# LFO_Schematic_Sheet_2.net
KiCad netlist of a schematic drawn in Altium Designer
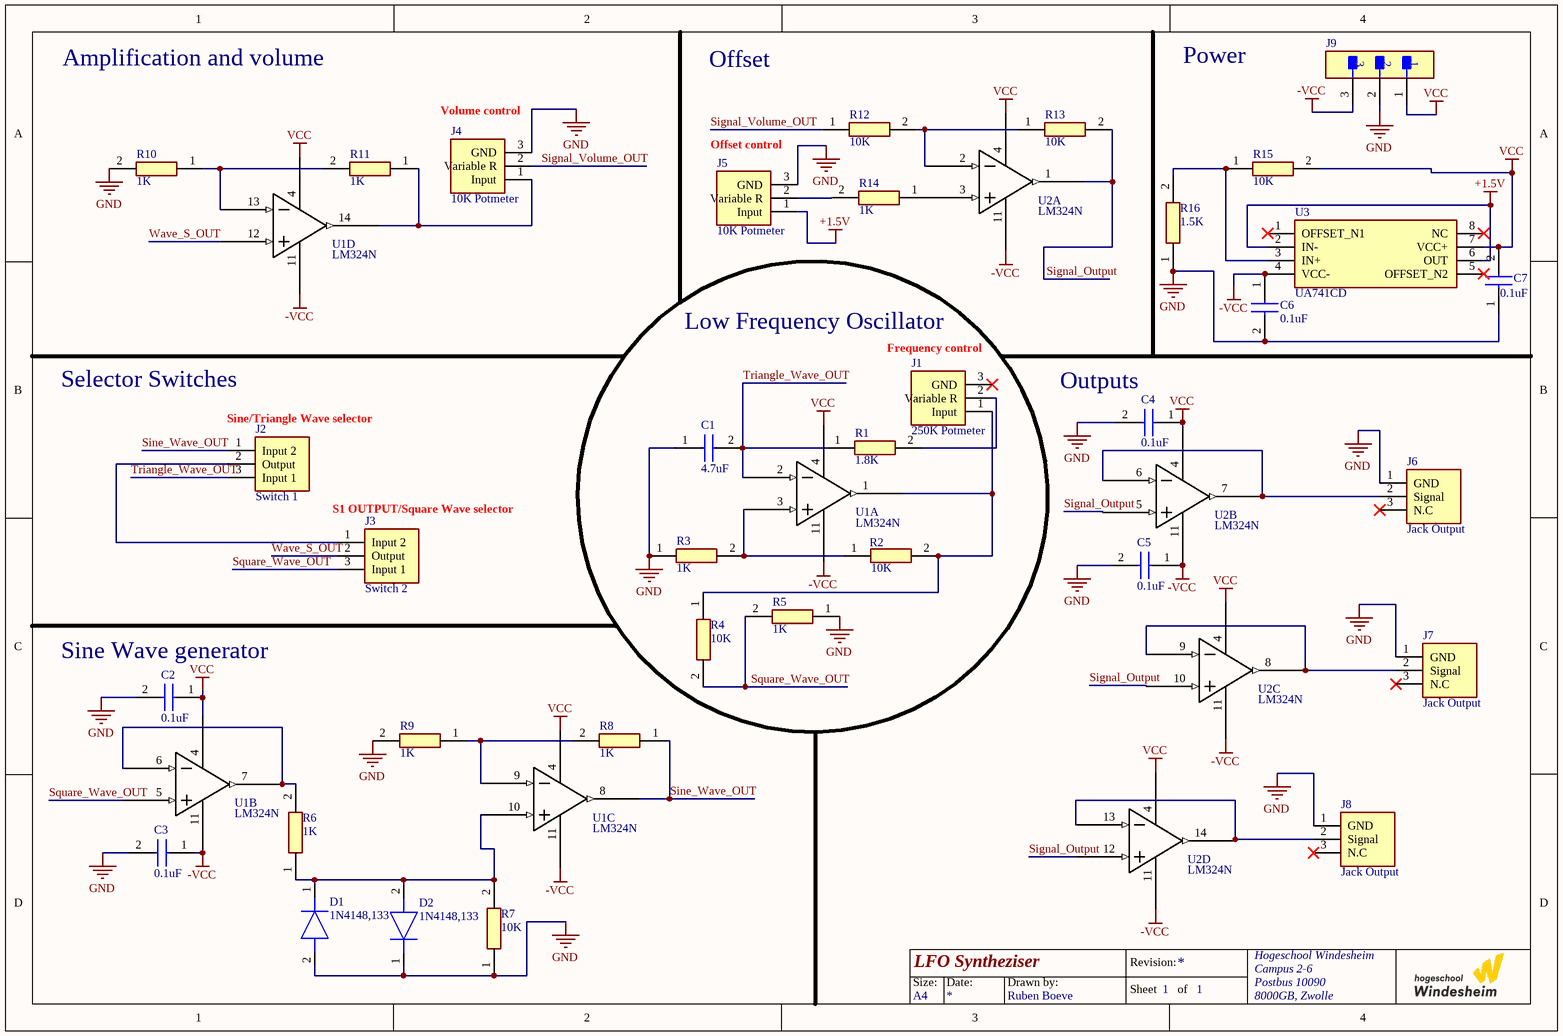
[diagram p0: LFO Schematic Sheet.2.SchDoc]

(export (version "E")
  (design (tool "Eeschema 10.0.6"))
  (components
    (comp (ref "C1")
      (value "4.7uF")
      (footprint "SamacSys:CAPC3216X180N")
      (description "Capacitor")
      (fields
        (field (name "MANUFACTURER_PART_NUMBER") "KGM31AR71H475KU")
        (field (name "MOUSER PART NUMBER") "581-KGM31AR71H475KU")
      )
      (libsource (lib "*") (part "KGM31AR71H475KU"))
    )
    (comp (ref "C2")
      (value "0.1uF")
      (footprint "SamacSys:C1206")
      (description "Capacitor")
      (fields
        (field (name "MANUFACTURER_PART_NUMBER") "C1206F104M4RACTU")
        (field (name "MOUSER PART NUMBER") "80-C1206F104M4R")
      )
      (libsource (lib "*") (part "C1206F104M4RACTU"))
    )
    (comp (ref "C3")
      (value "0.1uF")
      (footprint "SamacSys:C1206")
      (description "Capacitor")
      (fields
        (field (name "MANUFACTURER_PART_NUMBER") "C1206F104M4RACTU")
        (field (name "MOUSER PART NUMBER") "80-C1206F104M4R")
      )
      (libsource (lib "*") (part "C1206F104M4RACTU"))
    )
    (comp (ref "C4")
      (value "0.1uF")
      (footprint "SamacSys:C1206")
      (description "Capacitor")
      (fields
        (field (name "MANUFACTURER_PART_NUMBER") "C1206F104M4RACTU")
        (field (name "MOUSER PART NUMBER") "80-C1206F104M4R")
      )
      (libsource (lib "*") (part "C1206F104M4RACTU"))
    )
    (comp (ref "C5")
      (value "0.1uF")
      (footprint "SamacSys:C1206")
      (description "Capacitor")
      (fields
        (field (name "MANUFACTURER_PART_NUMBER") "C1206F104M4RACTU")
        (field (name "MOUSER PART NUMBER") "80-C1206F104M4R")
      )
      (libsource (lib "*") (part "C1206F104M4RACTU"))
    )
    (comp (ref "C6")
      (value "0.1uF")
      (footprint "SamacSys:C1206")
      (description "Capacitor")
      (fields
        (field (name "MANUFACTURER_PART_NUMBER") "C1206F104M4RACTU")
        (field (name "MOUSER PART NUMBER") "80-C1206F104M4R")
      )
      (libsource (lib "*") (part "C1206F104M4RACTU"))
    )
    (comp (ref "C7")
      (value "0.1uF")
      (footprint "SamacSys:C1206")
      (description "Capacitor")
      (fields
        (field (name "MANUFACTURER_PART_NUMBER") "C1206F104M4RACTU")
        (field (name "MOUSER PART NUMBER") "80-C1206F104M4R")
      )
      (libsource (lib "*") (part "C1206F104M4RACTU"))
    )
    (comp (ref "D1")
      (value "1N4148,133")
      (footprint "SamacSys:DIOAD1165W56L425D185")
      (description "Diode")
      (fields (field (name "MOUSER PART NUMBER") "771-1N4148,133"))
      (libsource (lib "*") (part "1N4148,133"))
    )
    (comp (ref "D2")
      (value "1N4148,133")
      (footprint "SamacSys:DIOAD1165W56L425D185")
      (description "Diode")
      (fields (field (name "MOUSER PART NUMBER") "771-1N4148,133"))
      (libsource (lib "*") (part "1N4148,133"))
    )
    (comp (ref "J1")
      (value "250K Potmeter")
      (footprint "SamacSys:SHDR3W50P0X200_1X3_650X240X440P")
      (description "Connector")
      (fields
        (field (name "MANUFACTURER_PART_NUMBER") "M22-7130342")
        (field (name "MOUSER PART NUMBER") "855-M22-7130342")
      )
      (libsource (lib "*") (part "M22-7130342"))
    )
    (comp (ref "J2")
      (value "Switch 1")
      (footprint "SamacSys:SHDR3W50P0X200_1X3_650X240X440P")
      (description "Connector")
      (fields
        (field (name "MANUFACTURER_PART_NUMBER") "M22-7130342")
        (field (name "MOUSER PART NUMBER") "855-M22-7130342")
      )
      (libsource (lib "") (part "M22-7130342_1"))
    )
    (comp (ref "J3")
      (value "Switch 2")
      (footprint "SamacSys:SHDR3W50P0X200_1X3_650X240X440P")
      (description "Connector")
      (fields
        (field (name "MANUFACTURER_PART_NUMBER") "M22-7130342")
        (field (name "MOUSER PART NUMBER") "855-M22-7130342")
      )
      (libsource (lib "") (part "M22-7130342_1"))
    )
    (comp (ref "J4")
      (value "10K Potmeter")
      (footprint "SamacSys:SHDR3W50P0X200_1X3_650X240X440P")
      (description "Connector")
      (fields
        (field (name "MANUFACTURER_PART_NUMBER") "M22-7130342")
        (field (name "MOUSER PART NUMBER") "855-M22-7130342")
      )
      (libsource (lib "*") (part "M22-7130342"))
    )
    (comp (ref "J5")
      (value "10K Potmeter")
      (footprint "SamacSys:SHDR3W50P0X200_1X3_650X240X440P")
      (description "Connector")
      (fields
        (field (name "MANUFACTURER_PART_NUMBER") "M22-7130342")
        (field (name "MOUSER PART NUMBER") "855-M22-7130342")
      )
      (libsource (lib "*") (part "M22-7130342"))
    )
    (comp (ref "J6")
      (value "Jack Output")
      (footprint "SamacSys:SHDR3W50P0X200_1X3_650X240X440P")
      (description "Connector")
      (fields
        (field (name "MANUFACTURER_PART_NUMBER") "M22-7130342")
        (field (name "MOUSER PART NUMBER") "855-M22-7130342")
      )
      (libsource (lib "") (part "M22-7130342_1"))
    )
    (comp (ref "J7")
      (value "Jack Output")
      (footprint "SamacSys:SHDR3W50P0X200_1X3_650X240X440P")
      (description "Connector")
      (fields
        (field (name "MANUFACTURER_PART_NUMBER") "M22-7130342")
        (field (name "MOUSER PART NUMBER") "855-M22-7130342")
      )
      (libsource (lib "") (part "M22-7130342_1"))
    )
    (comp (ref "J8")
      (value "Jack Output")
      (footprint "SamacSys:SHDR3W50P0X200_1X3_650X240X440P")
      (description "Connector")
      (fields
        (field (name "MANUFACTURER_PART_NUMBER") "M22-7130342")
        (field (name "MOUSER PART NUMBER") "855-M22-7130342")
      )
      (libsource (lib "") (part "M22-7130342_1"))
    )
    (comp (ref "J9")
      (value "B3B-XH-A(LF)(SN)")
      (footprint "FP-B3B-XH-A_LF_SN-MFG")
      (description "CONN HEADER VERT 3POS 2.5MM")
      (libsource (lib "Altium Content Vault") (part "0d3f023dd272f625e17a2be33dea85f"))
    )
    (comp (ref "R1")
      (value "1.8K")
      (footprint "SamacSys:ERJS08_U08_(1206)")
      (description "Moet 1.8K zijn")
      (fields (field (name "MANUFACTURER_PART_NUMBER") "ERJ-S08F1101V"))
      (libsource (lib "*") (part "ERJ-S08F1101V"))
    )
    (comp (ref "R2")
      (value "10K")
      (footprint "SamacSys:RESC3116X65N")
      (description "Resistor 1206")
      (fields
        (field (name "MANUFACTURER_PART_NUMBER") "RC1206FR-0710KL")
        (field (name "MOUSER PART NUMBER") "603-RC1206FR-0710KL")
      )
      (libsource (lib "") (part "RC1206FR-0710KL_2"))
    )
    (comp (ref "R3")
      (value "1K")
      (footprint "SamacSys:RCC1206_e3")
      (description "Resistor")
      (fields
        (field (name "MANUFACTURER_PART_NUMBER") "RCC12061K00FKEA")
        (field (name "MOUSER PART NUMBER") "71-RCC12061K00FKEA")
      )
      (libsource (lib "") (part "RCC12061K00FKEA_1"))
    )
    (comp (ref "R4")
      (value "10K")
      (footprint "SamacSys:RESC3116X65N")
      (description "Resistor 1206")
      (fields
        (field (name "MANUFACTURER_PART_NUMBER") "RC1206FR-0710KL")
        (field (name "MOUSER PART NUMBER") "603-RC1206FR-0710KL")
      )
      (libsource (lib "*") (part "RC1206FR-0710KL"))
    )
    (comp (ref "R5")
      (value "1K")
      (footprint "SamacSys:RCC1206_e3")
      (description "Resistor")
      (fields
        (field (name "MANUFACTURER_PART_NUMBER") "RCC12061K00FKEA")
        (field (name "MOUSER PART NUMBER") "71-RCC12061K00FKEA")
      )
      (libsource (lib "*") (part "RCC12061K00FKEA"))
    )
    (comp (ref "R6")
      (value "1K")
      (footprint "SamacSys:RCC1206_e3")
      (description "Resistor")
      (fields
        (field (name "MANUFACTURER_PART_NUMBER") "RCC12061K00FKEA")
        (field (name "MOUSER PART NUMBER") "71-RCC12061K00FKEA")
      )
      (libsource (lib "") (part "RCC12061K00FKEA_2"))
    )
    (comp (ref "R7")
      (value "10K")
      (footprint "SamacSys:RESC3116X65N")
      (description "Resistor 1206")
      (fields
        (field (name "MANUFACTURER_PART_NUMBER") "RC1206FR-0710KL")
        (field (name "MOUSER PART NUMBER") "603-RC1206FR-0710KL")
      )
      (libsource (lib "") (part "RC1206FR-0710KL_1"))
    )
    (comp (ref "R8")
      (value "1K")
      (footprint "SamacSys:RCC1206_e3")
      (description "Resistor")
      (fields
        (field (name "MANUFACTURER_PART_NUMBER") "RCC12061K00FKEA")
        (field (name "MOUSER PART NUMBER") "71-RCC12061K00FKEA")
      )
      (libsource (lib "*") (part "RCC12061K00FKEA"))
    )
    (comp (ref "R9")
      (value "1K")
      (footprint "SamacSys:RCC1206_e3")
      (description "Resistor")
      (fields
        (field (name "MANUFACTURER_PART_NUMBER") "RCC12061K00FKEA")
        (field (name "MOUSER PART NUMBER") "71-RCC12061K00FKEA")
      )
      (libsource (lib "*") (part "RCC12061K00FKEA"))
    )
    (comp (ref "R10")
      (value "1K")
      (footprint "SamacSys:RCC1206_e3")
      (description "Resistor")
      (fields
        (field (name "MANUFACTURER_PART_NUMBER") "RCC12061K00FKEA")
        (field (name "MOUSER PART NUMBER") "71-RCC12061K00FKEA")
      )
      (libsource (lib "*") (part "RCC12061K00FKEA"))
    )
    (comp (ref "R11")
      (value "1K")
      (footprint "SamacSys:RCC1206_e3")
      (description "Resistor")
      (fields
        (field (name "MANUFACTURER_PART_NUMBER") "RCC12061K00FKEA")
        (field (name "MOUSER PART NUMBER") "71-RCC12061K00FKEA")
      )
      (libsource (lib "*") (part "RCC12061K00FKEA"))
    )
    (comp (ref "R12")
      (value "10K")
      (footprint "SamacSys:RESC3116X65N")
      (description "Resistor 1206")
      (fields
        (field (name "MANUFACTURER_PART_NUMBER") "RC1206FR-0710KL")
        (field (name "MOUSER PART NUMBER") "603-RC1206FR-0710KL")
      )
      (libsource (lib "") (part "RC1206FR-0710KL_2"))
    )
    (comp (ref "R13")
      (value "10K")
      (footprint "SamacSys:RESC3116X65N")
      (description "Resistor 1206")
      (fields
        (field (name "MANUFACTURER_PART_NUMBER") "RC1206FR-0710KL")
        (field (name "MOUSER PART NUMBER") "603-RC1206FR-0710KL")
      )
      (libsource (lib "") (part "RC1206FR-0710KL_2"))
    )
    (comp (ref "R14")
      (value "1K")
      (footprint "SamacSys:RCC1206_e3")
      (description "Resistor")
      (fields
        (field (name "MANUFACTURER_PART_NUMBER") "RCC12061K00FKEA")
        (field (name "MOUSER PART NUMBER") "71-RCC12061K00FKEA")
      )
      (libsource (lib "*") (part "RCC12061K00FKEA"))
    )
    (comp (ref "R15")
      (value "10K")
      (footprint "SamacSys:RESC3116X65N")
      (description "Resistor 1206")
      (fields
        (field (name "MANUFACTURER_PART_NUMBER") "RC1206FR-0710KL")
        (field (name "MOUSER PART NUMBER") "603-RC1206FR-0710KL")
      )
      (libsource (lib "") (part "RC1206FR-0710KL_2"))
    )
    (comp (ref "R16")
      (value "1.5K")
      (footprint "SamacSys:RESC3246X60N")
      (description "Resistor")
      (fields (field (name "MANUFACTURER_PART_NUMBER") "CRCW12181K50JNEK"))
      (libsource (lib "*") (part "CRCW12181K50JNEK"))
    )
    (comp (ref "U1")
      (value "LM324N")
      (footprint "SOIC127P600X175-14N")
      (description "Quad Op-Amp")
      (fields
        (field (name "MANUFACTURER_PART_NUMBER") "LM324M/NOPB")
        (field (name "MOUSER PART NUMBER") "926-LM324M/NOPB")
      )
      (libsource (lib "MyLibrary") (part "LM324N"))
    )
    (comp (ref "U2")
      (value "LM324N")
      (footprint "SOIC127P600X175-14N")
      (description "Quad Op-Amp")
      (fields
        (field (name "MANUFACTURER_PART_NUMBER") "LM324M/NOPB")
        (field (name "MOUSER PART NUMBER") "926-LM324M/NOPB")
      )
      (libsource (lib "MyLibrary") (part "LM324N"))
    )
    (comp (ref "U3")
      (value "UA741CD")
      (footprint "SamacSys:SOIC127P600X175-8N")
      (description "Integrated Circuit")
      (fields (field (name "MOUSER PART NUMBER") "595-UA741CD"))
      (libsource (lib "*") (part "UA741CD"))
    )
  )
  (nets
    (net (code "1") (name "+1.5V") (class "Default")
      (node (ref "J5") (pin "1") (pinfunction "Input_1") (pintype "passive"))
      (node (ref "U3") (pin "2") (pinfunction "IN-_2") (pintype "passive"))
      (node (ref "U3") (pin "6") (pinfunction "OUT_6") (pintype "passive"))
    )
    (net (code "2") (name "-VCC") (class "Default")
      (node (ref "C3") (pin "1") (pinfunction "1_1") (pintype "passive"))
      (node (ref "C5") (pin "1") (pinfunction "1_1") (pintype "passive"))
      (node (ref "C6") (pin "1") (pinfunction "1_1") (pintype "passive"))
      (node (ref "J9") (pin "3") (pinfunction "3_3") (pintype "passive"))
      (node (ref "U1") (pin "11") (pinfunction "GND_11") (pintype "power_in"))
      (node (ref "U2") (pin "11") (pinfunction "GND_11") (pintype "power_in"))
      (node (ref "U3") (pin "4") (pinfunction "VCC-_4") (pintype "passive"))
    )
    (net (code "3") (name "/Signal_Output") (class "Default")
      (node (ref "R13") (pin "2") (pinfunction "2_2") (pintype "passive"))
      (node (ref "U2") (pin "1") (pinfunction "Out_1") (pintype "output"))
      (node (ref "U2") (pin "10") (pinfunction "+_10") (pintype "input"))
      (node (ref "U2") (pin "12") (pinfunction "+_12") (pintype "input"))
      (node (ref "U2") (pin "5") (pinfunction "+_5") (pintype "input"))
    )
    (net (code "4") (name "/Signal_Volume_OUT") (class "Default")
      (node (ref "J4") (pin "2") (pinfunction "Variable_R_2") (pintype "passive"))
      (node (ref "R12") (pin "1") (pinfunction "1_1") (pintype "passive"))
    )
    (net (code "5") (name "/Sine_Wave_OUT") (class "Default")
      (node (ref "J2") (pin "1") (pinfunction "Input_2_1") (pintype "passive"))
      (node (ref "R8") (pin "1") (pinfunction "1_1") (pintype "passive"))
      (node (ref "U1") (pin "8") (pinfunction "Out_8") (pintype "output"))
    )
    (net (code "6") (name "/Square_Wave_OUT") (class "Default")
      (node (ref "J3") (pin "3") (pinfunction "Input_1_3") (pintype "passive"))
      (node (ref "R4") (pin "2") (pinfunction "2_2") (pintype "passive"))
      (node (ref "R5") (pin "2") (pinfunction "2_2") (pintype "passive"))
      (node (ref "U1") (pin "5") (pinfunction "+_5") (pintype "input"))
    )
    (net (code "7") (name "/Triangle_Wave_OUT") (class "Default")
      (node (ref "C1") (pin "2") (pinfunction "2_2") (pintype "passive"))
      (node (ref "J2") (pin "3") (pinfunction "Input_1_3") (pintype "passive"))
      (node (ref "R1") (pin "1") (pinfunction "1_1") (pintype "passive"))
      (node (ref "U1") (pin "2") (pinfunction "-_2") (pintype "input"))
    )
    (net (code "8") (name "/Wave_S_OUT") (class "Default")
      (node (ref "J3") (pin "2") (pinfunction "Output_2") (pintype "passive"))
      (node (ref "U1") (pin "12") (pinfunction "+_12") (pintype "input"))
    )
    (net (code "9") (name "GND") (class "Default")
      (node (ref "C1") (pin "1") (pinfunction "1_1") (pintype "passive"))
      (node (ref "C2") (pin "2") (pinfunction "2_2") (pintype "passive"))
      (node (ref "C3") (pin "2") (pinfunction "2_2") (pintype "passive"))
      (node (ref "C4") (pin "2") (pinfunction "2_2") (pintype "passive"))
      (node (ref "C5") (pin "2") (pinfunction "2_2") (pintype "passive"))
      (node (ref "C6") (pin "2") (pinfunction "2_2") (pintype "passive"))
      (node (ref "C7") (pin "1") (pinfunction "1_1") (pintype "passive"))
      (node (ref "D1") (pin "2") (pinfunction "A_2") (pintype "passive"))
      (node (ref "D2") (pin "1") (pinfunction "K_1") (pintype "passive"))
      (node (ref "J4") (pin "3") (pinfunction "GND_3") (pintype "passive"))
      (node (ref "J5") (pin "3") (pinfunction "GND_3") (pintype "passive"))
      (node (ref "J6") (pin "1") (pinfunction "Input_2_1") (pintype "passive"))
      (node (ref "J7") (pin "1") (pinfunction "Input_2_1") (pintype "passive"))
      (node (ref "J8") (pin "1") (pinfunction "Input_2_1") (pintype "passive"))
      (node (ref "J9") (pin "2") (pinfunction "2_2") (pintype "passive"))
      (node (ref "R10") (pin "2") (pinfunction "2_2") (pintype "passive"))
      (node (ref "R16") (pin "1") (pinfunction "1_1") (pintype "passive"))
      (node (ref "R3") (pin "1") (pinfunction "1_1") (pintype "passive"))
      (node (ref "R5") (pin "1") (pinfunction "1_1") (pintype "passive"))
      (node (ref "R7") (pin "1") (pinfunction "1_1") (pintype "passive"))
      (node (ref "R9") (pin "2") (pinfunction "2_2") (pintype "passive"))
    )
    (net (code "10") (name "Net-(D1-K)") (class "Default")
      (node (ref "D1") (pin "1") (pinfunction "K_1") (pintype "passive"))
      (node (ref "D2") (pin "2") (pinfunction "A_2") (pintype "passive"))
      (node (ref "R6") (pin "1") (pinfunction "1_1") (pintype "passive"))
      (node (ref "R7") (pin "2") (pinfunction "2_2") (pintype "passive"))
      (node (ref "U1") (pin "10") (pinfunction "+_10") (pintype "input"))
    )
    (net (code "11") (name "Net-(J1-Input)") (class "Default")
      (node (ref "J1") (pin "1") (pinfunction "Input_1") (pintype "passive"))
      (node (ref "R2") (pin "2") (pinfunction "2_2") (pintype "passive"))
      (node (ref "R4") (pin "1") (pinfunction "1_1") (pintype "passive"))
      (node (ref "U1") (pin "1") (pinfunction "Out_1") (pintype "output"))
    )
    (net (code "12") (name "Net-(J1-Variable_R)") (class "Default")
      (node (ref "J1") (pin "2") (pinfunction "Variable_R_2") (pintype "passive"))
      (node (ref "R1") (pin "2") (pinfunction "2_2") (pintype "passive"))
    )
    (net (code "13") (name "Net-(J2-Output)") (class "Default")
      (node (ref "J2") (pin "2") (pinfunction "Output_2") (pintype "passive"))
      (node (ref "J3") (pin "1") (pinfunction "Input_2_1") (pintype "passive"))
    )
    (net (code "14") (name "Net-(J4-Input)") (class "Default")
      (node (ref "J4") (pin "1") (pinfunction "Input_1") (pintype "passive"))
      (node (ref "R11") (pin "1") (pinfunction "1_1") (pintype "passive"))
      (node (ref "U1") (pin "14") (pinfunction "Out_14") (pintype "output"))
    )
    (net (code "15") (name "Net-(J5-Variable_R)") (class "Default")
      (node (ref "J5") (pin "2") (pinfunction "Variable_R_2") (pintype "passive"))
      (node (ref "R14") (pin "2") (pinfunction "2_2") (pintype "passive"))
    )
    (net (code "16") (name "Net-(J6-Output)") (class "Default")
      (node (ref "J6") (pin "2") (pinfunction "Output_2") (pintype "passive"))
      (node (ref "U2") (pin "6") (pinfunction "-_6") (pintype "input"))
      (node (ref "U2") (pin "7") (pinfunction "Out_7") (pintype "output"))
    )
    (net (code "17") (name "Net-(J7-Output)") (class "Default")
      (node (ref "J7") (pin "2") (pinfunction "Output_2") (pintype "passive"))
      (node (ref "U2") (pin "8") (pinfunction "Out_8") (pintype "output"))
      (node (ref "U2") (pin "9") (pinfunction "-_9") (pintype "input"))
    )
    (net (code "18") (name "Net-(J8-Output)") (class "Default")
      (node (ref "J8") (pin "2") (pinfunction "Output_2") (pintype "passive"))
      (node (ref "U2") (pin "13") (pinfunction "-_13") (pintype "input"))
      (node (ref "U2") (pin "14") (pinfunction "Out_14") (pintype "output"))
    )
    (net (code "19") (name "Net-(U1A-+)") (class "Default")
      (node (ref "R2") (pin "1") (pinfunction "1_1") (pintype "passive"))
      (node (ref "R3") (pin "2") (pinfunction "2_2") (pintype "passive"))
      (node (ref "U1") (pin "3") (pinfunction "+_3") (pintype "input"))
    )
    (net (code "20") (name "Net-(U1B--)") (class "Default")
      (node (ref "R6") (pin "2") (pinfunction "2_2") (pintype "passive"))
      (node (ref "U1") (pin "6") (pinfunction "-_6") (pintype "input"))
      (node (ref "U1") (pin "7") (pinfunction "Out_7") (pintype "output"))
    )
    (net (code "21") (name "Net-(U1C--)") (class "Default")
      (node (ref "R8") (pin "2") (pinfunction "2_2") (pintype "passive"))
      (node (ref "R9") (pin "1") (pinfunction "1_1") (pintype "passive"))
      (node (ref "U1") (pin "9") (pinfunction "-_9") (pintype "input"))
    )
    (net (code "22") (name "Net-(U1D--)") (class "Default")
      (node (ref "R10") (pin "1") (pinfunction "1_1") (pintype "passive"))
      (node (ref "R11") (pin "2") (pinfunction "2_2") (pintype "passive"))
      (node (ref "U1") (pin "13") (pinfunction "-_13") (pintype "input"))
    )
    (net (code "23") (name "Net-(U2A-+)") (class "Default")
      (node (ref "R14") (pin "1") (pinfunction "1_1") (pintype "passive"))
      (node (ref "U2") (pin "3") (pinfunction "+_3") (pintype "input"))
    )
    (net (code "24") (name "Net-(U2A--)") (class "Default")
      (node (ref "R12") (pin "2") (pinfunction "2_2") (pintype "passive"))
      (node (ref "R13") (pin "1") (pinfunction "1_1") (pintype "passive"))
      (node (ref "U2") (pin "2") (pinfunction "-_2") (pintype "input"))
    )
    (net (code "25") (name "Net-(U3-IN+)") (class "Default")
      (node (ref "R15") (pin "1") (pinfunction "1_1") (pintype "passive"))
      (node (ref "R16") (pin "2") (pinfunction "2_2") (pintype "passive"))
      (node (ref "U3") (pin "3") (pinfunction "IN+_3") (pintype "passive"))
    )
    (net (code "26") (name "VCC") (class "Default")
      (node (ref "C2") (pin "1") (pinfunction "1_1") (pintype "passive"))
      (node (ref "C4") (pin "1") (pinfunction "1_1") (pintype "passive"))
      (node (ref "C7") (pin "2") (pinfunction "2_2") (pintype "passive"))
      (node (ref "J9") (pin "1") (pinfunction "1_1") (pintype "passive"))
      (node (ref "R15") (pin "2") (pinfunction "2_2") (pintype "passive"))
      (node (ref "U1") (pin "4") (pinfunction "VCC_4") (pintype "power_in"))
      (node (ref "U2") (pin "4") (pinfunction "VCC_4") (pintype "power_in"))
      (node (ref "U3") (pin "7") (pinfunction "VCC+_7") (pintype "passive"))
    )
    (net (code "27") (name "unconnected-(J1-GND-Pad3)") (class "Default")
      (node (ref "J1") (pin "3") (pinfunction "GND_3") (pintype "passive+no_connect"))
    )
    (net (code "28") (name "unconnected-(J6-Input_1-Pad3)") (class "Default")
      (node (ref "J6") (pin "3") (pinfunction "Input_1_3") (pintype "passive+no_connect"))
    )
    (net (code "29") (name "unconnected-(J7-Input_1-Pad3)") (class "Default")
      (node (ref "J7") (pin "3") (pinfunction "Input_1_3") (pintype "passive+no_connect"))
    )
    (net (code "30") (name "unconnected-(J8-Input_1-Pad3)") (class "Default")
      (node (ref "J8") (pin "3") (pinfunction "Input_1_3") (pintype "passive+no_connect"))
    )
    (net (code "31") (name "unconnected-(U3-NC-Pad8)") (class "Default")
      (node (ref "U3") (pin "8") (pinfunction "NC_8") (pintype "passive+no_connect"))
    )
    (net (code "32") (name "unconnected-(U3-OFFSET_N1-Pad1)") (class "Default")
      (node (ref "U3") (pin "1") (pinfunction "OFFSET_N1_1") (pintype "passive+no_connect"))
    )
    (net (code "33") (name "unconnected-(U3-OFFSET_N2-Pad5)") (class "Default")
      (node (ref "U3") (pin "5") (pinfunction "OFFSET_N2_5") (pintype "passive+no_connect"))
    )
  )
)
